# M401X.net
KiCad netlist of a schematic drawn in EAGLE
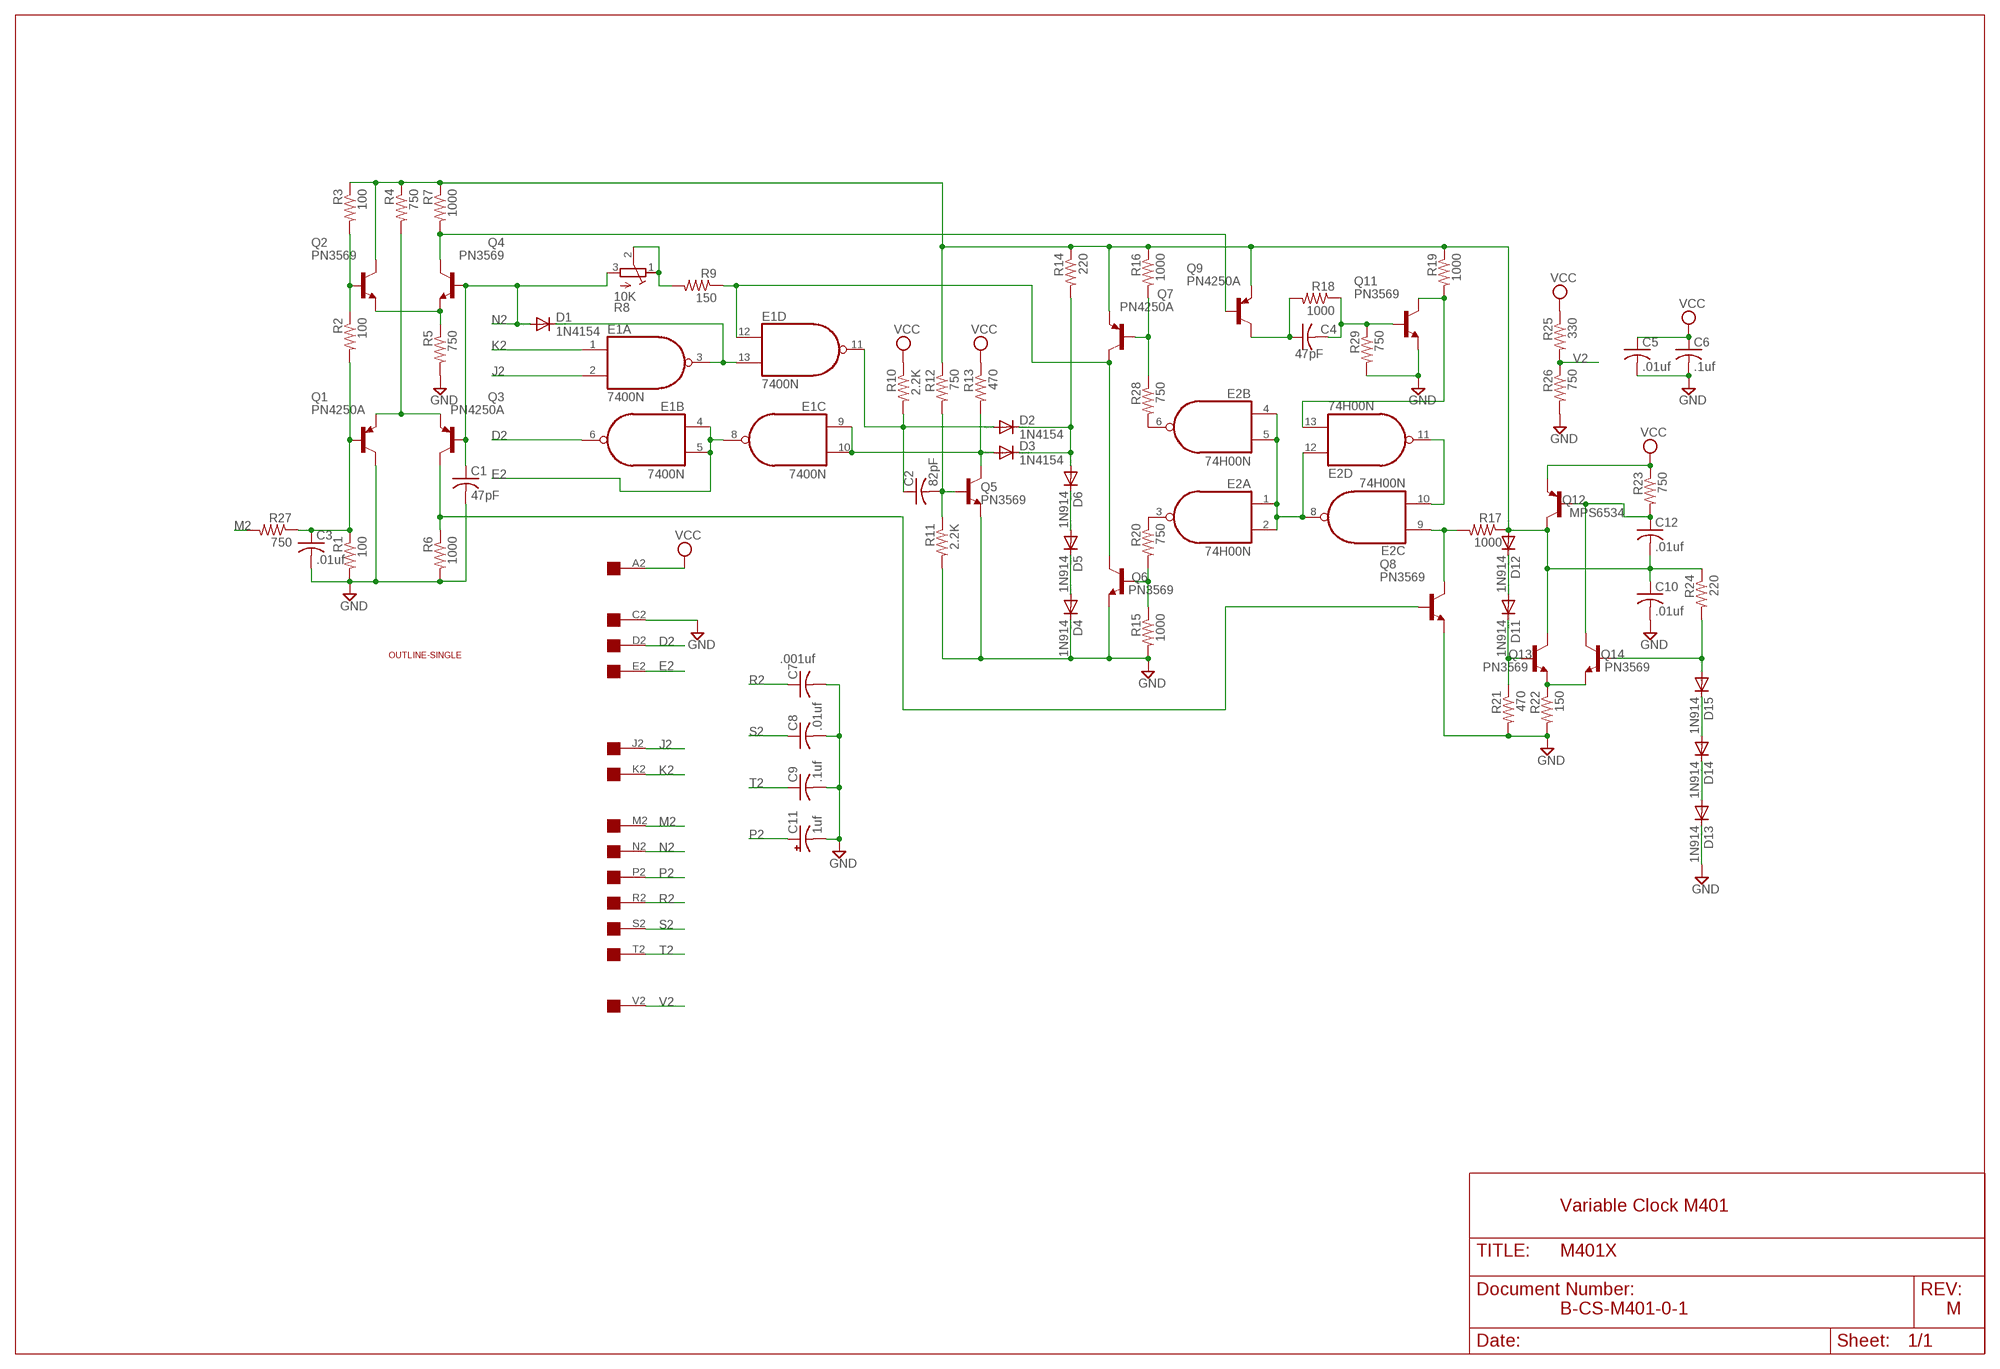
[diagram p0: schematic, sheet 1]

(export (version "E")
  (design (tool "Eeschema 10.0.6"))
  (components
    (comp (ref "C1")
      (value "47pF")
      (footprint "eagle-import:C050-025X075")
      (libsource (lib "eagle-import") (part "C-US050-025X075"))
    )
    (comp (ref "C2")
      (value "82pF")
      (footprint "eagle-import:C050-025X075")
      (libsource (lib "eagle-import") (part "C-US050-025X075"))
    )
    (comp (ref "C3")
      (value ".01uf")
      (footprint "eagle-import:C050-025X075")
      (libsource (lib "eagle-import") (part "C-US050-025X075"))
    )
    (comp (ref "C4")
      (value "47pF")
      (footprint "eagle-import:C050-025X075")
      (libsource (lib "eagle-import") (part "C-US050-025X075"))
    )
    (comp (ref "C5")
      (value ".01uf")
      (footprint "eagle-import:C050-025X075")
      (libsource (lib "eagle-import") (part "C-US050-025X075"))
    )
    (comp (ref "C6")
      (value ".1uf")
      (footprint "eagle-import:C102-043X133")
      (libsource (lib "eagle-import") (part "C-US102-043X133"))
    )
    (comp (ref "C7")
      (value ".001uf")
      (footprint "eagle-import:C050-025X075")
      (libsource (lib "eagle-import") (part "C-US050-025X075"))
    )
    (comp (ref "C8")
      (value ".01uf")
      (footprint "eagle-import:C225-062X268")
      (libsource (lib "eagle-import") (part "C-US225-062X268"))
    )
    (comp (ref "C9")
      (value ".1uf")
      (footprint "eagle-import:C275-093X316")
      (libsource (lib "eagle-import") (part "C-US275-093X316"))
    )
    (comp (ref "C10")
      (value ".01uf")
      (footprint "eagle-import:C050-025X075")
      (libsource (lib "eagle-import") (part "C-US050-025X075"))
    )
    (comp (ref "C11")
      (value "1uf")
      (footprint "eagle-import:E15-5")
      (libsource (lib "eagle-import") (part "CPOL-USE15-5AXIAL"))
    )
    (comp (ref "C12")
      (value ".01uf")
      (footprint "eagle-import:C050-025X075")
      (libsource (lib "eagle-import") (part "C-US050-025X075"))
    )
    (comp (ref "D1")
      (value "1N4154")
      (footprint "eagle-import:DO35-10")
      (libsource (lib "eagle-import") (part "1N4148DO35-10"))
    )
    (comp (ref "D2")
      (value "1N4154")
      (footprint "eagle-import:DO35-10")
      (libsource (lib "eagle-import") (part "1N4148DO35-10"))
    )
    (comp (ref "D3")
      (value "1N4154")
      (footprint "eagle-import:DO35-10")
      (libsource (lib "eagle-import") (part "1N4148DO35-10"))
    )
    (comp (ref "D4")
      (value "1N914")
      (footprint "eagle-import:DO35-10")
      (libsource (lib "eagle-import") (part "1N4148DO35-10"))
    )
    (comp (ref "D5")
      (value "1N914")
      (footprint "eagle-import:DO35-10")
      (libsource (lib "eagle-import") (part "1N4148DO35-10"))
    )
    (comp (ref "D6")
      (value "1N914")
      (footprint "eagle-import:DO35-10")
      (libsource (lib "eagle-import") (part "1N4148DO35-10"))
    )
    (comp (ref "D11")
      (value "1N914")
      (footprint "eagle-import:DO35-10")
      (libsource (lib "eagle-import") (part "1N4148DO35-10"))
    )
    (comp (ref "D12")
      (value "1N914")
      (footprint "eagle-import:DO35-10")
      (libsource (lib "eagle-import") (part "1N4148DO35-10"))
    )
    (comp (ref "D13")
      (value "1N914")
      (footprint "eagle-import:DO35-10")
      (libsource (lib "eagle-import") (part "1N4148DO35-10"))
    )
    (comp (ref "D14")
      (value "1N914")
      (footprint "eagle-import:DO35-10")
      (libsource (lib "eagle-import") (part "1N4148DO35-10"))
    )
    (comp (ref "D15")
      (value "1N914")
      (footprint "eagle-import:DO35-10")
      (libsource (lib "eagle-import") (part "1N4148DO35-10"))
    )
    (comp (ref "E1")
      (value "7400N")
      (footprint "eagle-import:DIL14")
      (libsource (lib "eagle-import") (part "7400N"))
    )
    (comp (ref "E2")
      (value "74H00N")
      (footprint "eagle-import:DIL14")
      (libsource (lib "eagle-import") (part "7400N"))
    )
    (comp (ref "Q1")
      (value "PN4250A")
      (footprint "eagle-import:TO39")
      (libsource (lib "eagle-import") (part "-PNP-TO39-EBC2N3637"))
    )
    (comp (ref "Q2")
      (value "PN3569")
      (footprint "eagle-import:TO39")
      (libsource (lib "eagle-import") (part "-NPN-TO39-EBC2N3019"))
    )
    (comp (ref "Q3")
      (value "PN4250A")
      (footprint "eagle-import:TO39")
      (libsource (lib "eagle-import") (part "-PNP-TO39-EBC2N3637"))
    )
    (comp (ref "Q4")
      (value "PN3569")
      (footprint "eagle-import:TO39")
      (libsource (lib "eagle-import") (part "-NPN-TO39-EBC2N3019"))
    )
    (comp (ref "Q5")
      (value "PN3569")
      (footprint "eagle-import:TO39")
      (libsource (lib "eagle-import") (part "-NPN-TO39-EBC2N3019"))
    )
    (comp (ref "Q6")
      (value "PN3569")
      (footprint "eagle-import:TO39")
      (libsource (lib "eagle-import") (part "-NPN-TO39-EBC2N3019"))
    )
    (comp (ref "Q7")
      (value "PN4250A")
      (footprint "eagle-import:TO39")
      (libsource (lib "eagle-import") (part "-PNP-TO39-EBC2N3637"))
    )
    (comp (ref "Q8")
      (value "PN3569")
      (footprint "eagle-import:TO39")
      (libsource (lib "eagle-import") (part "-NPN-TO39-EBC2N3019"))
    )
    (comp (ref "Q9")
      (value "PN4250A")
      (footprint "eagle-import:TO39")
      (libsource (lib "eagle-import") (part "-PNP-TO39-EBC2N3637"))
    )
    (comp (ref "Q11")
      (value "PN3569")
      (footprint "eagle-import:TO39")
      (libsource (lib "eagle-import") (part "-NPN-TO39-EBC2N3019"))
    )
    (comp (ref "Q12")
      (value "MPS6534")
      (footprint "eagle-import:TO39")
      (libsource (lib "eagle-import") (part "-PNP-TO39-EBC2N3637"))
    )
    (comp (ref "Q13")
      (value "PN3569")
      (footprint "eagle-import:TO39")
      (libsource (lib "eagle-import") (part "-NPN-TO39-EBC2N3019"))
    )
    (comp (ref "Q14")
      (value "PN3569")
      (footprint "eagle-import:TO39")
      (libsource (lib "eagle-import") (part "-NPN-TO39-EBC2N3019"))
    )
    (comp (ref "R1")
      (value "100")
      (footprint "eagle-import:0207_10")
      (libsource (lib "eagle-import") (part "R-US_0207/10"))
    )
    (comp (ref "R2")
      (value "100")
      (footprint "eagle-import:0207_10")
      (libsource (lib "eagle-import") (part "R-US_0207/10"))
    )
    (comp (ref "R3")
      (value "100")
      (footprint "eagle-import:0207_10")
      (libsource (lib "eagle-import") (part "R-US_0207/10"))
    )
    (comp (ref "R4")
      (value "750")
      (footprint "eagle-import:0207_10")
      (libsource (lib "eagle-import") (part "R-US_0207/10"))
    )
    (comp (ref "R5")
      (value "750")
      (footprint "eagle-import:0207_10")
      (libsource (lib "eagle-import") (part "R-US_0207/10"))
    )
    (comp (ref "R6")
      (value "1000")
      (footprint "eagle-import:0207_10")
      (libsource (lib "eagle-import") (part "R-US_0207/10"))
    )
    (comp (ref "R7")
      (value "1000")
      (footprint "eagle-import:0207_10")
      (libsource (lib "eagle-import") (part "R-US_0207/10"))
    )
    (comp (ref "R8")
      (value "10K")
      (footprint "eagle-import:3006Y")
      (libsource (lib "eagle-import") (part "275P"))
    )
    (comp (ref "R9")
      (value "150")
      (footprint "eagle-import:0207_10")
      (libsource (lib "eagle-import") (part "R-US_0207/10"))
    )
    (comp (ref "R10")
      (value "2.2K")
      (footprint "eagle-import:0207_10")
      (libsource (lib "eagle-import") (part "R-US_0207/10"))
    )
    (comp (ref "R11")
      (value "2.2K")
      (footprint "eagle-import:0207_10")
      (libsource (lib "eagle-import") (part "R-US_0207/10"))
    )
    (comp (ref "R12")
      (value "750")
      (footprint "eagle-import:0207_10")
      (libsource (lib "eagle-import") (part "R-US_0207/10"))
    )
    (comp (ref "R13")
      (value "470")
      (footprint "eagle-import:0207_10")
      (libsource (lib "eagle-import") (part "R-US_0207/10"))
    )
    (comp (ref "R14")
      (value "220")
      (footprint "eagle-import:0207_10")
      (libsource (lib "eagle-import") (part "R-US_0207/10"))
    )
    (comp (ref "R15")
      (value "1000")
      (footprint "eagle-import:0207_10")
      (libsource (lib "eagle-import") (part "R-US_0207/10"))
    )
    (comp (ref "R16")
      (value "1000")
      (footprint "eagle-import:0207_10")
      (libsource (lib "eagle-import") (part "R-US_0207/10"))
    )
    (comp (ref "R17")
      (value "1000")
      (footprint "eagle-import:0207_10")
      (libsource (lib "eagle-import") (part "R-US_0207/10"))
    )
    (comp (ref "R18")
      (value "1000")
      (footprint "eagle-import:0207_10")
      (libsource (lib "eagle-import") (part "R-US_0207/10"))
    )
    (comp (ref "R19")
      (value "1000")
      (footprint "eagle-import:0207_10")
      (libsource (lib "eagle-import") (part "R-US_0207/10"))
    )
    (comp (ref "R20")
      (value "750")
      (footprint "eagle-import:0207_10")
      (libsource (lib "eagle-import") (part "R-US_0207/10"))
    )
    (comp (ref "R21")
      (value "470")
      (footprint "eagle-import:0207_10")
      (libsource (lib "eagle-import") (part "R-US_0207/10"))
    )
    (comp (ref "R22")
      (value "150")
      (footprint "eagle-import:0207_10")
      (libsource (lib "eagle-import") (part "R-US_0207/10"))
    )
    (comp (ref "R23")
      (value "750")
      (footprint "eagle-import:0207_10")
      (libsource (lib "eagle-import") (part "R-US_0207/10"))
    )
    (comp (ref "R24")
      (value "220")
      (footprint "eagle-import:0207_10")
      (libsource (lib "eagle-import") (part "R-US_0207/10"))
    )
    (comp (ref "R25")
      (value "330")
      (footprint "eagle-import:0207_10")
      (libsource (lib "eagle-import") (part "R-US_0207/10"))
    )
    (comp (ref "R26")
      (value "750")
      (footprint "eagle-import:0207_10")
      (libsource (lib "eagle-import") (part "R-US_0207/10"))
    )
    (comp (ref "R27")
      (value "750")
      (footprint "eagle-import:0207_10")
      (libsource (lib "eagle-import") (part "R-US_0207/10"))
    )
    (comp (ref "R28")
      (value "750")
      (footprint "eagle-import:0207_10")
      (libsource (lib "eagle-import") (part "R-US_0207/10"))
    )
    (comp (ref "R29")
      (value "750")
      (footprint "eagle-import:0207_10")
      (libsource (lib "eagle-import") (part "R-US_0207/10"))
    )
    (comp (ref "U$1")
      (value "OUTLINE-SINGLE")
      (footprint "eagle-import:SINGLE")
      (libsource (lib "eagle-import") (part "OUTLINE-SINGLE"))
    )
    (comp (ref "U$2")
      (value "EDGE-1")
      (footprint "eagle-import:EDGE-CON1")
      (libsource (lib "eagle-import") (part "EDGE-1"))
    )
  )
  (nets
    (net (code "1") (name "/D2") (class "Default")
      (node (ref "E1") (pin "6") (pinfunction "O_6") (pintype "output"))
      (node (ref "U$2") (pin "D2") (pinfunction "1_D2") (pintype "bidirectional"))
    )
    (net (code "2") (name "/E2") (class "Default")
      (node (ref "E1") (pin "4") (pinfunction "I0_4") (pintype "input"))
      (node (ref "E1") (pin "5") (pinfunction "I1_5") (pintype "input"))
      (node (ref "E1") (pin "8") (pinfunction "O_8") (pintype "output"))
      (node (ref "U$2") (pin "E2") (pinfunction "1_E2") (pintype "bidirectional"))
    )
    (net (code "3") (name "/J2") (class "Default")
      (node (ref "E1") (pin "2") (pinfunction "I1_2") (pintype "input"))
      (node (ref "U$2") (pin "J2") (pinfunction "1_J2") (pintype "bidirectional"))
    )
    (net (code "4") (name "/K2") (class "Default")
      (node (ref "E1") (pin "1") (pinfunction "I0_1") (pintype "input"))
      (node (ref "U$2") (pin "K2") (pinfunction "1_K2") (pintype "bidirectional"))
    )
    (net (code "5") (name "/M2") (class "Default")
      (node (ref "R27") (pin "2") (pinfunction "2_2") (pintype "passive"))
      (node (ref "U$2") (pin "M2") (pinfunction "1_M2") (pintype "bidirectional"))
    )
    (net (code "6") (name "/N2") (class "Default")
      (node (ref "C1") (pin "1") (pinfunction "1_1") (pintype "passive"))
      (node (ref "D1") (pin "A") (pinfunction "A_A") (pintype "passive"))
      (node (ref "Q3") (pin "2") (pinfunction "B_2") (pintype "passive"))
      (node (ref "Q4") (pin "2") (pinfunction "B_2") (pintype "passive"))
      (node (ref "R8") (pin "3") (pinfunction "E_3") (pintype "passive"))
      (node (ref "U$2") (pin "N2") (pinfunction "1_N2") (pintype "bidirectional"))
    )
    (net (code "7") (name "/P2") (class "Default")
      (node (ref "C11") (pin "+") (pinfunction "+_+") (pintype "passive"))
      (node (ref "U$2") (pin "P2") (pinfunction "1_P2") (pintype "bidirectional"))
    )
    (net (code "8") (name "/R2") (class "Default")
      (node (ref "C7") (pin "1") (pinfunction "1_1") (pintype "passive"))
      (node (ref "U$2") (pin "R2") (pinfunction "1_R2") (pintype "bidirectional"))
    )
    (net (code "9") (name "/S2") (class "Default")
      (node (ref "C8") (pin "1") (pinfunction "1_1") (pintype "passive"))
      (node (ref "U$2") (pin "S2") (pinfunction "1_S2") (pintype "bidirectional"))
    )
    (net (code "10") (name "/T2") (class "Default")
      (node (ref "C9") (pin "1") (pinfunction "1_1") (pintype "passive"))
      (node (ref "U$2") (pin "T2") (pinfunction "1_T2") (pintype "bidirectional"))
    )
    (net (code "11") (name "/V2") (class "Default")
      (node (ref "R25") (pin "2") (pinfunction "2_2") (pintype "passive"))
      (node (ref "R26") (pin "1") (pinfunction "1_1") (pintype "passive"))
      (node (ref "U$2") (pin "V2") (pinfunction "1_V2") (pintype "bidirectional"))
    )
    (net (code "12") (name "GND") (class "Default")
      (node (ref "C1") (pin "2") (pinfunction "2_2") (pintype "passive"))
      (node (ref "C10") (pin "2") (pinfunction "2_2") (pintype "passive"))
      (node (ref "C11") (pin "-") (pinfunction "-_-") (pintype "passive"))
      (node (ref "C3") (pin "2") (pinfunction "2_2") (pintype "passive"))
      (node (ref "C5") (pin "2") (pinfunction "2_2") (pintype "passive"))
      (node (ref "C6") (pin "2") (pinfunction "2_2") (pintype "passive"))
      (node (ref "C7") (pin "2") (pinfunction "2_2") (pintype "passive"))
      (node (ref "C8") (pin "2") (pinfunction "2_2") (pintype "passive"))
      (node (ref "C9") (pin "2") (pinfunction "2_2") (pintype "passive"))
      (node (ref "D13") (pin "C") (pinfunction "C_C") (pintype "passive"))
      (node (ref "D4") (pin "C") (pinfunction "C_C") (pintype "passive"))
      (node (ref "Q1") (pin "3") (pinfunction "C_3") (pintype "passive"))
      (node (ref "Q11") (pin "1") (pinfunction "E_1") (pintype "passive"))
      (node (ref "Q5") (pin "1") (pinfunction "E_1") (pintype "passive"))
      (node (ref "Q6") (pin "1") (pinfunction "E_1") (pintype "passive"))
      (node (ref "Q8") (pin "1") (pinfunction "E_1") (pintype "passive"))
      (node (ref "R1") (pin "2") (pinfunction "2_2") (pintype "passive"))
      (node (ref "R11") (pin "2") (pinfunction "2_2") (pintype "passive"))
      (node (ref "R15") (pin "2") (pinfunction "2_2") (pintype "passive"))
      (node (ref "R21") (pin "2") (pinfunction "2_2") (pintype "passive"))
      (node (ref "R22") (pin "2") (pinfunction "2_2") (pintype "passive"))
      (node (ref "R26") (pin "2") (pinfunction "2_2") (pintype "passive"))
      (node (ref "R29") (pin "2") (pinfunction "2_2") (pintype "passive"))
      (node (ref "R5") (pin "2") (pinfunction "2_2") (pintype "passive"))
      (node (ref "R6") (pin "2") (pinfunction "2_2") (pintype "passive"))
      (node (ref "U$2") (pin "C2") (pinfunction "1_C2") (pintype "bidirectional"))
    )
    (net (code "13") (name "Net-(D2-PadC)") (class "Default")
      (node (ref "D2") (pin "C") (pinfunction "C_C") (pintype "passive"))
      (node (ref "D3") (pin "C") (pinfunction "C_C") (pintype "passive"))
      (node (ref "D6") (pin "A") (pinfunction "A_A") (pintype "passive"))
      (node (ref "R14") (pin "2") (pinfunction "2_2") (pintype "passive"))
    )
    (net (code "14") (name "Net-(D4-PadA)") (class "Default")
      (node (ref "D4") (pin "A") (pinfunction "A_A") (pintype "passive"))
      (node (ref "D5") (pin "C") (pinfunction "C_C") (pintype "passive"))
    )
    (net (code "15") (name "Net-(D5-PadA)") (class "Default")
      (node (ref "D5") (pin "A") (pinfunction "A_A") (pintype "passive"))
      (node (ref "D6") (pin "C") (pinfunction "C_C") (pintype "passive"))
    )
    (net (code "16") (name "Net-(D11-PadA)") (class "Default")
      (node (ref "D11") (pin "A") (pinfunction "A_A") (pintype "passive"))
      (node (ref "D12") (pin "C") (pinfunction "C_C") (pintype "passive"))
    )
    (net (code "17") (name "Net-(D13-PadA)") (class "Default")
      (node (ref "D13") (pin "A") (pinfunction "A_A") (pintype "passive"))
      (node (ref "D14") (pin "C") (pinfunction "C_C") (pintype "passive"))
    )
    (net (code "18") (name "Net-(D14-PadA)") (class "Default")
      (node (ref "D14") (pin "A") (pinfunction "A_A") (pintype "passive"))
      (node (ref "D15") (pin "C") (pinfunction "C_C") (pintype "passive"))
    )
    (net (code "19") (name "Net-(E1A-O)") (class "Default")
      (node (ref "D1") (pin "C") (pinfunction "C_C") (pintype "passive"))
      (node (ref "E1") (pin "13") (pinfunction "I1_13") (pintype "input"))
      (node (ref "E1") (pin "3") (pinfunction "O_3") (pintype "output"))
    )
    (net (code "20") (name "Net-(E1C-I0)") (class "Default")
      (node (ref "D3") (pin "A") (pinfunction "A_A") (pintype "passive"))
      (node (ref "E1") (pin "10") (pinfunction "I1_10") (pintype "input"))
      (node (ref "E1") (pin "9") (pinfunction "I0_9") (pintype "input"))
      (node (ref "Q5") (pin "3") (pinfunction "C_3") (pintype "passive"))
      (node (ref "R13") (pin "2") (pinfunction "2_2") (pintype "passive"))
    )
    (net (code "21") (name "Net-(E1D-I0)") (class "Default")
      (node (ref "E1") (pin "12") (pinfunction "I0_12") (pintype "input"))
      (node (ref "Q6") (pin "3") (pinfunction "C_3") (pintype "passive"))
      (node (ref "Q7") (pin "3") (pinfunction "C_3") (pintype "passive"))
      (node (ref "R9") (pin "1") (pinfunction "1_1") (pintype "passive"))
    )
    (net (code "22") (name "Net-(E1D-O)") (class "Default")
      (node (ref "C2") (pin "1") (pinfunction "1_1") (pintype "passive"))
      (node (ref "D2") (pin "A") (pinfunction "A_A") (pintype "passive"))
      (node (ref "E1") (pin "11") (pinfunction "O_11") (pintype "output"))
      (node (ref "R10") (pin "2") (pinfunction "2_2") (pintype "passive"))
    )
    (net (code "23") (name "Net-(E2A-I0)") (class "Default")
      (node (ref "E2") (pin "1") (pinfunction "I0_1") (pintype "input"))
      (node (ref "E2") (pin "12") (pinfunction "I0_12") (pintype "input"))
      (node (ref "E2") (pin "2") (pinfunction "I1_2") (pintype "input"))
      (node (ref "E2") (pin "4") (pinfunction "I0_4") (pintype "input"))
      (node (ref "E2") (pin "5") (pinfunction "I1_5") (pintype "input"))
      (node (ref "E2") (pin "8") (pinfunction "O_8") (pintype "output"))
    )
    (net (code "24") (name "Net-(E2A-O)") (class "Default")
      (node (ref "E2") (pin "3") (pinfunction "O_3") (pintype "output"))
      (node (ref "R20") (pin "1") (pinfunction "1_1") (pintype "passive"))
    )
    (net (code "25") (name "Net-(E2B-O)") (class "Default")
      (node (ref "E2") (pin "6") (pinfunction "O_6") (pintype "output"))
      (node (ref "R28") (pin "2") (pinfunction "2_2") (pintype "passive"))
    )
    (net (code "26") (name "Net-(E2C-I0)") (class "Default")
      (node (ref "E2") (pin "9") (pinfunction "I0_9") (pintype "input"))
      (node (ref "Q8") (pin "3") (pinfunction "C_3") (pintype "passive"))
      (node (ref "R17") (pin "2") (pinfunction "2_2") (pintype "passive"))
    )
    (net (code "27") (name "Net-(E2C-I1)") (class "Default")
      (node (ref "E2") (pin "10") (pinfunction "I1_10") (pintype "input"))
      (node (ref "E2") (pin "11") (pinfunction "O_11") (pintype "output"))
    )
    (net (code "28") (name "Net-(E2D-I1)") (class "Default")
      (node (ref "E2") (pin "13") (pinfunction "I1_13") (pintype "input"))
      (node (ref "Q11") (pin "3") (pinfunction "C_3") (pintype "passive"))
      (node (ref "R19") (pin "2") (pinfunction "2_2") (pintype "passive"))
    )
    (net (code "29") (name "Net-(Q1-B)") (class "Default")
      (node (ref "C3") (pin "1") (pinfunction "1_1") (pintype "passive"))
      (node (ref "Q1") (pin "2") (pinfunction "B_2") (pintype "passive"))
      (node (ref "R1") (pin "1") (pinfunction "1_1") (pintype "passive"))
      (node (ref "R2") (pin "2") (pinfunction "2_2") (pintype "passive"))
      (node (ref "R27") (pin "1") (pinfunction "1_1") (pintype "passive"))
    )
    (net (code "30") (name "Net-(Q1-E)") (class "Default")
      (node (ref "Q1") (pin "1") (pinfunction "E_1") (pintype "passive"))
      (node (ref "Q3") (pin "1") (pinfunction "E_1") (pintype "passive"))
      (node (ref "R4") (pin "2") (pinfunction "2_2") (pintype "passive"))
    )
    (net (code "31") (name "Net-(Q2-B)") (class "Default")
      (node (ref "Q2") (pin "2") (pinfunction "B_2") (pintype "passive"))
      (node (ref "R2") (pin "1") (pinfunction "1_1") (pintype "passive"))
      (node (ref "R3") (pin "2") (pinfunction "2_2") (pintype "passive"))
    )
    (net (code "32") (name "Net-(Q2-E)") (class "Default")
      (node (ref "Q2") (pin "1") (pinfunction "E_1") (pintype "passive"))
      (node (ref "Q4") (pin "1") (pinfunction "E_1") (pintype "passive"))
      (node (ref "R5") (pin "1") (pinfunction "1_1") (pintype "passive"))
    )
    (net (code "33") (name "Net-(Q3-C)") (class "Default")
      (node (ref "Q3") (pin "3") (pinfunction "C_3") (pintype "passive"))
      (node (ref "Q8") (pin "2") (pinfunction "B_2") (pintype "passive"))
      (node (ref "R6") (pin "1") (pinfunction "1_1") (pintype "passive"))
    )
    (net (code "34") (name "Net-(Q4-C)") (class "Default")
      (node (ref "Q4") (pin "3") (pinfunction "C_3") (pintype "passive"))
      (node (ref "Q9") (pin "2") (pinfunction "B_2") (pintype "passive"))
      (node (ref "R7") (pin "2") (pinfunction "2_2") (pintype "passive"))
    )
    (net (code "35") (name "Net-(Q5-B)") (class "Default")
      (node (ref "C2") (pin "2") (pinfunction "2_2") (pintype "passive"))
      (node (ref "Q5") (pin "2") (pinfunction "B_2") (pintype "passive"))
      (node (ref "R11") (pin "1") (pinfunction "1_1") (pintype "passive"))
      (node (ref "R12") (pin "2") (pinfunction "2_2") (pintype "passive"))
    )
    (net (code "36") (name "Net-(Q6-B)") (class "Default")
      (node (ref "Q6") (pin "2") (pinfunction "B_2") (pintype "passive"))
      (node (ref "R15") (pin "1") (pinfunction "1_1") (pintype "passive"))
      (node (ref "R20") (pin "2") (pinfunction "2_2") (pintype "passive"))
    )
    (net (code "37") (name "Net-(Q7-B)") (class "Default")
      (node (ref "Q7") (pin "2") (pinfunction "B_2") (pintype "passive"))
      (node (ref "R16") (pin "2") (pinfunction "2_2") (pintype "passive"))
      (node (ref "R28") (pin "1") (pinfunction "1_1") (pintype "passive"))
    )
    (net (code "38") (name "Net-(Q9-C)") (class "Default")
      (node (ref "C4") (pin "1") (pinfunction "1_1") (pintype "passive"))
      (node (ref "Q9") (pin "3") (pinfunction "C_3") (pintype "passive"))
      (node (ref "R18") (pin "2") (pinfunction "2_2") (pintype "passive"))
    )
    (net (code "39") (name "Net-(Q11-B)") (class "Default")
      (node (ref "C4") (pin "2") (pinfunction "2_2") (pintype "passive"))
      (node (ref "Q11") (pin "2") (pinfunction "B_2") (pintype "passive"))
      (node (ref "R18") (pin "1") (pinfunction "1_1") (pintype "passive"))
      (node (ref "R29") (pin "1") (pinfunction "1_1") (pintype "passive"))
    )
    (net (code "40") (name "Net-(Q12-B)") (class "Default")
      (node (ref "C12") (pin "1") (pinfunction "1_1") (pintype "passive"))
      (node (ref "Q12") (pin "2") (pinfunction "B_2") (pintype "passive"))
      (node (ref "Q14") (pin "3") (pinfunction "C_3") (pintype "passive"))
      (node (ref "R23") (pin "2") (pinfunction "2_2") (pintype "passive"))
    )
    (net (code "41") (name "Net-(Q12-C)") (class "Default")
      (node (ref "C10") (pin "1") (pinfunction "1_1") (pintype "passive"))
      (node (ref "C12") (pin "2") (pinfunction "2_2") (pintype "passive"))
      (node (ref "D12") (pin "A") (pinfunction "A_A") (pintype "passive"))
      (node (ref "Q12") (pin "3") (pinfunction "C_3") (pintype "passive"))
      (node (ref "Q13") (pin "3") (pinfunction "C_3") (pintype "passive"))
      (node (ref "Q2") (pin "3") (pinfunction "C_3") (pintype "passive"))
      (node (ref "Q7") (pin "1") (pinfunction "E_1") (pintype "passive"))
      (node (ref "Q9") (pin "1") (pinfunction "E_1") (pintype "passive"))
      (node (ref "R12") (pin "1") (pinfunction "1_1") (pintype "passive"))
      (node (ref "R14") (pin "1") (pinfunction "1_1") (pintype "passive"))
      (node (ref "R16") (pin "1") (pinfunction "1_1") (pintype "passive"))
      (node (ref "R17") (pin "1") (pinfunction "1_1") (pintype "passive"))
      (node (ref "R19") (pin "1") (pinfunction "1_1") (pintype "passive"))
      (node (ref "R24") (pin "1") (pinfunction "1_1") (pintype "passive"))
      (node (ref "R3") (pin "1") (pinfunction "1_1") (pintype "passive"))
      (node (ref "R4") (pin "1") (pinfunction "1_1") (pintype "passive"))
      (node (ref "R7") (pin "1") (pinfunction "1_1") (pintype "passive"))
    )
    (net (code "42") (name "Net-(Q13-B)") (class "Default")
      (node (ref "D11") (pin "C") (pinfunction "C_C") (pintype "passive"))
      (node (ref "Q13") (pin "2") (pinfunction "B_2") (pintype "passive"))
      (node (ref "R21") (pin "1") (pinfunction "1_1") (pintype "passive"))
    )
    (net (code "43") (name "Net-(Q13-E)") (class "Default")
      (node (ref "Q13") (pin "1") (pinfunction "E_1") (pintype "passive"))
      (node (ref "Q14") (pin "1") (pinfunction "E_1") (pintype "passive"))
      (node (ref "R22") (pin "1") (pinfunction "1_1") (pintype "passive"))
    )
    (net (code "44") (name "Net-(Q14-B)") (class "Default")
      (node (ref "D15") (pin "A") (pinfunction "A_A") (pintype "passive"))
      (node (ref "Q14") (pin "2") (pinfunction "B_2") (pintype "passive"))
      (node (ref "R24") (pin "2") (pinfunction "2_2") (pintype "passive"))
    )
    (net (code "45") (name "Net-(R8-A)") (class "Default")
      (node (ref "R8") (pin "1") (pinfunction "A_1") (pintype "passive"))
      (node (ref "R8") (pin "2") (pinfunction "S_2") (pintype "passive"))
      (node (ref "R9") (pin "2") (pinfunction "2_2") (pintype "passive"))
    )
    (net (code "46") (name "VCC") (class "Default")
      (node (ref "C5") (pin "1") (pinfunction "1_1") (pintype "passive"))
      (node (ref "C6") (pin "1") (pinfunction "1_1") (pintype "passive"))
      (node (ref "Q12") (pin "1") (pinfunction "E_1") (pintype "passive"))
      (node (ref "R10") (pin "1") (pinfunction "1_1") (pintype "passive"))
      (node (ref "R13") (pin "1") (pinfunction "1_1") (pintype "passive"))
      (node (ref "R23") (pin "1") (pinfunction "1_1") (pintype "passive"))
      (node (ref "R25") (pin "1") (pinfunction "1_1") (pintype "passive"))
      (node (ref "U$2") (pin "A2") (pinfunction "1_A2") (pintype "bidirectional"))
    )
  )
)
